# Frogduino_Atmega1284_R2_EasyEDA_Model.net
KiCad netlist of a schematic drawn in EasyEDA Pro
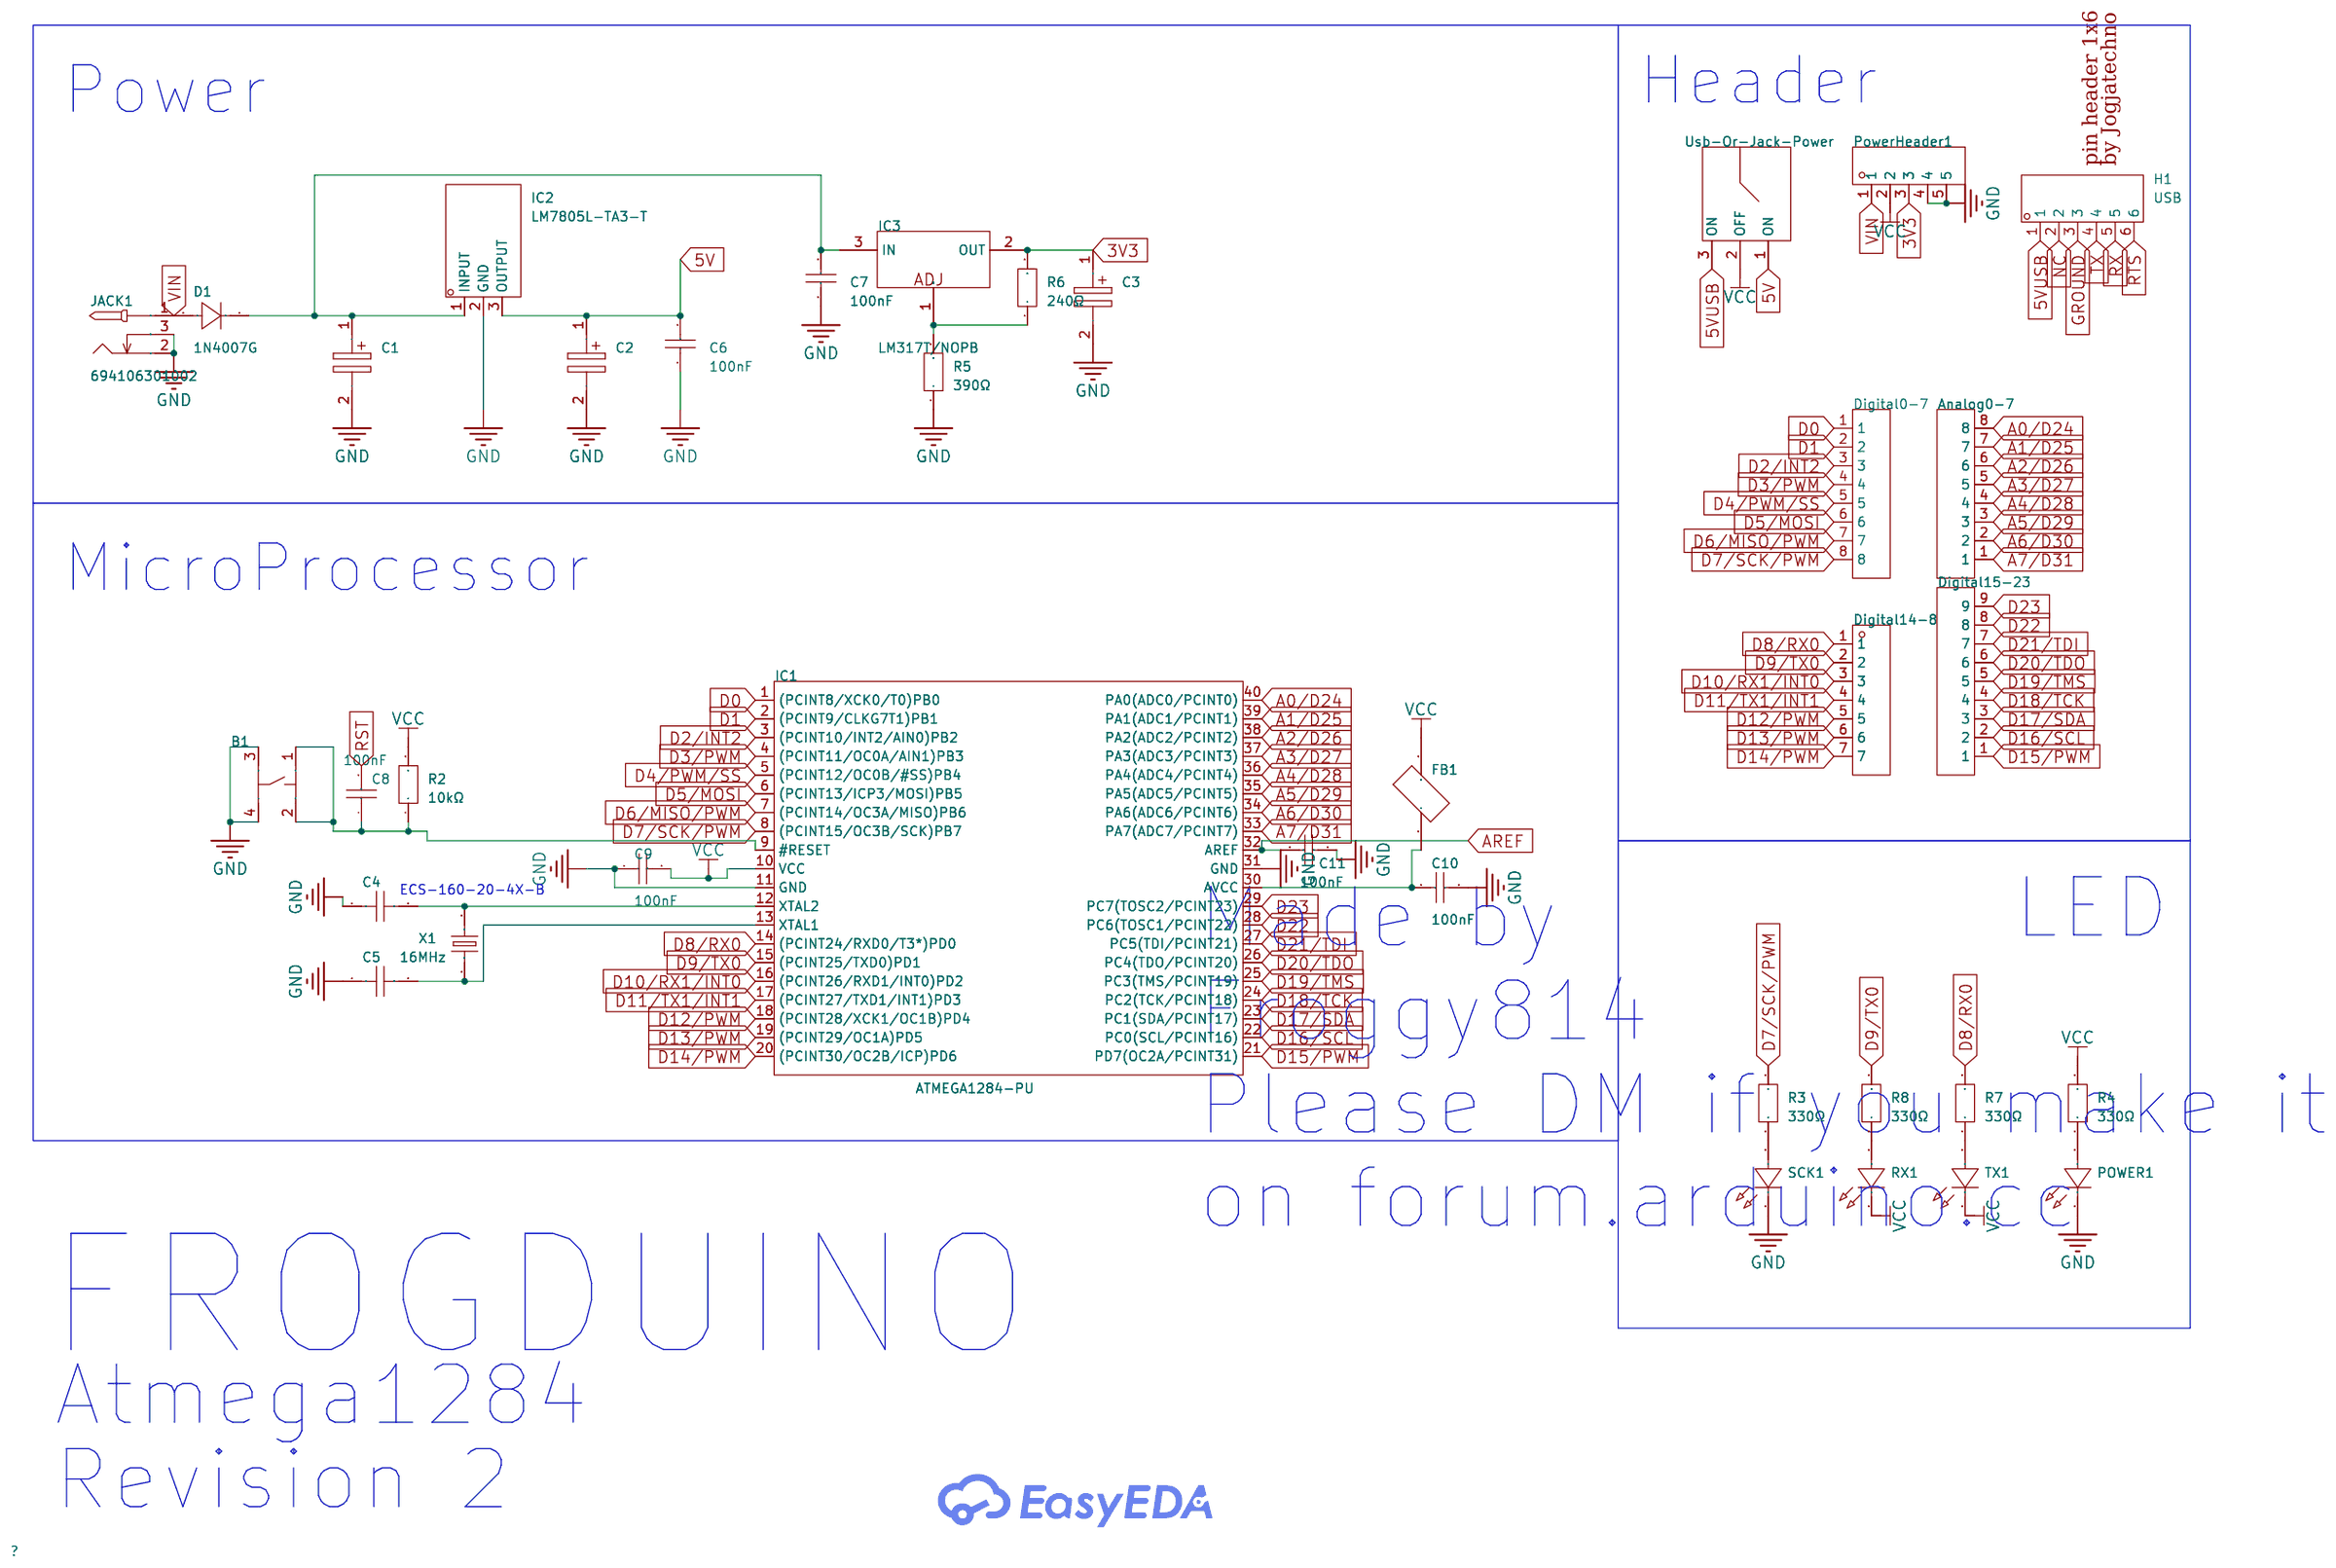
[diagram p0: schematic sheet]

(export (version "E")
  (design (tool "Eeschema 10.0.6"))
  (components
    (comp (ref "Analog0-7")
      (value "排母HDR1X8-2.54")
      (footprint "easyedapro:HDR-TH_8P-P2.54-V-F")
      (libsource (lib "easyedapro") (part "排母HDR1X8-2.54"))
    )
    (comp (ref "B1")
      (value "TS02-66-43-BK-100-SCR-D")
      (footprint "easyedapro:SW-TH_4P-L6.0-W6.0-P4.50-LS6.5")
      (fields (field (name "Manufacturer") "CUI"))
      (libsource (lib "easyedapro") (part "TS02-66-43-BK-100-SCR-D"))
    )
    (comp (ref "C1")
      (value "~")
      (footprint "easyedapro:CAPPM7344X310N")
      (libsource (lib "easyedapro") (part "TAJD107K016SNJV_"))
    )
    (comp (ref "C2")
      (value "~")
      (footprint "easyedapro:CAPPM7344X310N")
      (libsource (lib "easyedapro") (part "TAJD107K016SNJV_"))
    )
    (comp (ref "C3")
      (value "~")
      (footprint "easyedapro:CAPPM7344X310N")
      (libsource (lib "easyedapro") (part "TAJD107K016SNJV_"))
    )
    (comp (ref "C4")
      (value "C0805C220J4HACTU")
      (footprint "easyedapro:C1210")
      (libsource (lib "easyedapro") (part "C1210C220J5GACTU"))
    )
    (comp (ref "C5")
      (value "C0805C220J4HACTU")
      (footprint "easyedapro:C1210")
      (libsource (lib "easyedapro") (part "C1210C220J5GACTU"))
    )
    (comp (ref "C6")
      (value "100nF")
      (footprint "easyedapro:C1206")
      (description "Capacitance:100nF Tolerance:±10% Tolerance:±10% Voltage Rating:100V Temperature Coefficient:X7R")
      (fields (field (name "Manufacturer Part") "1206B104K101CT") (field (name "Manufacturer") "Walsin(华新科)"))
      (libsource (lib "easyedapro") (part "1206B104K101"))
    )
    (comp (ref "C7")
      (value "100nF")
      (footprint "easyedapro:C1206")
      (description "Capacitance:100nF Tolerance:±10% Tolerance:±10% Voltage Rating:100V Temperature Coefficient:X7R")
      (fields (field (name "Manufacturer Part") "1206B104K101CT") (field (name "Manufacturer") "Walsin(华新科)"))
      (libsource (lib "easyedapro") (part "1206B104K101"))
    )
    (comp (ref "C8")
      (value "100nF")
      (footprint "easyedapro:C1206")
      (description "Capacitance:100nF Tolerance:±10% Tolerance:±10% Voltage Rating:100V Temperature Coefficient:X7R")
      (fields (field (name "Manufacturer Part") "1206B104K101CT") (field (name "Manufacturer") "Walsin(华新科)"))
      (libsource (lib "easyedapro") (part "1206B104K101"))
    )
    (comp (ref "C9")
      (value "100nF")
      (footprint "easyedapro:C1206")
      (description "Capacitance:100nF Tolerance:±10% Tolerance:±10% Voltage Rating:100V Temperature Coefficient:X7R")
      (fields (field (name "Manufacturer Part") "1206B104K101CT") (field (name "Manufacturer") "Walsin(华新科)"))
      (libsource (lib "easyedapro") (part "1206B104K101"))
    )
    (comp (ref "C10")
      (value "100nF")
      (footprint "easyedapro:C1206")
      (description "Capacitance:100nF Tolerance:±10% Tolerance:±10% Voltage Rating:100V Temperature Coefficient:X7R")
      (fields (field (name "Manufacturer Part") "1206B104K101CT") (field (name "Manufacturer") "Walsin(华新科)"))
      (libsource (lib "easyedapro") (part "1206B104K101"))
    )
    (comp (ref "C11")
      (value "100nF")
      (footprint "easyedapro:C1206")
      (description "Capacitance:100nF Tolerance:±10% Tolerance:±10% Voltage Rating:100V Temperature Coefficient:X7R")
      (fields (field (name "Manufacturer Part") "1206B104K101CT") (field (name "Manufacturer") "Walsin(华新科)"))
      (libsource (lib "easyedapro") (part "1206B104K101"))
    )
    (comp (ref "D1")
      (value "1N4007G")
      (footprint "easyedapro:DO-41_BD2.4-L4.7-P8.70-D0.6-RD")
      (libsource (lib "easyedapro") (part "1N4007G_C2764732"))
    )
    (comp (ref "Digital0-7")
      (value "排母HDR1X8-2.54")
      (footprint "easyedapro:HDR-TH_8P-P2.54-V-F")
      (libsource (lib "easyedapro") (part "排母HDR1X8-2.54"))
    )
    (comp (ref "Digital14-8")
      (value "2.54-1*7P/30mm(3+24+3)")
      (footprint "easyedapro:HDR-TH_7P-P2.54-V-M-1")
      (libsource (lib "easyedapro") (part "2.54-1*7P/30MM(3+24+3)"))
    )
    (comp (ref "Digital15-23")
      (value "KH-2.54PH180-1X9P-L11.5")
      (footprint "easyedapro:HDR-TH_9P-P2.54-V-M")
      (fields (field (name "Manufacturer") "kinghelm(金航标)"))
      (libsource (lib "easyedapro") (part "KH-2.54PH180-1X9P-L11.5"))
    )
    (comp (ref "FB1")
      (value "~")
      (footprint "easyedapro:FB_28L0138-70R-10")
      (libsource (lib "easyedapro") (part "28L0138-70R-10_"))
    )
    (comp (ref "H1")
      (value "USB")
      (fields
        (field (name "Manufacturer Part") "Headers  Pins1x6P 2.54mm")
        (field (name "Manufacturer") "ReliaPro")
      )
      (libsource (lib "easyedapro") (part "Headers  Pins1x6P 2.54mm"))
    )
    (comp (ref "IC1")
      (value "ATMEGA1284-PU")
      (footprint "easyedapro:CONN-SMD_40P-P2.54_C9900007166")
      (fields (field (name "Manufacturer") "MICROCHIP(美国微芯)"))
      (libsource (lib "easyedapro") (part "ATMEGA1284-PU"))
    )
    (comp (ref "IC2")
      (value "LM7805L-TA3-T")
      (footprint "easyedapro:TO-220IS_L10.16-W4.7-P2.54-L")
      (description "Output Type:-")
      (libsource (lib "easyedapro") (part "LM7805L-TA3-T_C340686"))
    )
    (comp (ref "IC3")
      (value "LM317T/NOPB")
      (footprint "easyedapro:TO-220-3_L10.2-W4.6-P2.54-L")
      (fields (field (name "Manufacturer") "TI(德州仪器)"))
      (libsource (lib "easyedapro") (part "LM317T/NOPB"))
    )
    (comp (ref "JACK1")
      (value "694106301002")
      (footprint "easyedapro:CONN-TH_694106301002")
      (fields (field (name "Manufacturer") "würth Elektronik"))
      (libsource (lib "easyedapro") (part "694106301002"))
    )
    (comp (ref "POWER1")
      (value "SML-811UTT86C")
      (footprint "easyedapro:LED-SMD_L3.4-W1.3-RD")
      (fields (field (name "Manufacturer") "ROHM(罗姆)"))
      (libsource (lib "easyedapro") (part "SML-811UTT86C"))
    )
    (comp (ref "PowerHeader1")
      (value "2.54mm1*5PHeader")
      (footprint "easyedapro:HDR-TH_5P-P2.54-V")
      (fields (field (name "Manufacturer") "ReliaPro"))
      (libsource (lib "easyedapro") (part "2&quot;42 OLED - DIY More"))
    )
    (comp (ref "R2")
      (value "10kΩ")
      (footprint "easyedapro:R2512")
      (fields (field (name "Manufacturer Part") "AS25J1002ET") (field (name "Manufacturer") "Ohmite"))
      (libsource (lib "easyedapro") (part "AS25J1002ET"))
    )
    (comp (ref "R3")
      (value "330Ω")
      (footprint "easyedapro:R2010")
      (fields (field (name "Manufacturer Part") "RC2010JK-07330RL") (field (name "Manufacturer") "YAGEO(国巨)"))
      (libsource (lib "easyedapro") (part "RC2010JK-07330RL"))
    )
    (comp (ref "R4")
      (value "330Ω")
      (footprint "easyedapro:R2010")
      (fields (field (name "Manufacturer Part") "RC2010JK-07330RL") (field (name "Manufacturer") "YAGEO(国巨)"))
      (libsource (lib "easyedapro") (part "RC2010JK-07330RL"))
    )
    (comp (ref "R5")
      (value "390Ω")
      (footprint "easyedapro:R2512")
      (fields
        (field (name "Manufacturer Part") "CRGP2512F390R")
        (field (name "Manufacturer") "TE Connectivity(泰科电子)")
      )
      (libsource (lib "easyedapro") (part "CRGP2512F390R"))
    )
    (comp (ref "R6")
      (value "240Ω")
      (footprint "easyedapro:R2512")
      (fields (field (name "Manufacturer Part") "RK73H3ATTE2400F") (field (name "Manufacturer") "KOA"))
      (libsource (lib "easyedapro") (part "RK73H3ATTE2400F"))
    )
    (comp (ref "R7")
      (value "330Ω")
      (footprint "easyedapro:R2010")
      (fields (field (name "Manufacturer Part") "RC2010JK-07330RL") (field (name "Manufacturer") "YAGEO(国巨)"))
      (libsource (lib "easyedapro") (part "RC2010JK-07330RL"))
    )
    (comp (ref "R8")
      (value "330Ω")
      (footprint "easyedapro:R2010")
      (fields (field (name "Manufacturer Part") "RC2010JK-07330RL") (field (name "Manufacturer") "YAGEO(国巨)"))
      (libsource (lib "easyedapro") (part "RC2010JK-07330RL"))
    )
    (comp (ref "RX1")
      (value "SML-811UTT86C")
      (footprint "easyedapro:LED-SMD_L3.4-W1.3-RD")
      (fields (field (name "Manufacturer") "ROHM(罗姆)"))
      (libsource (lib "easyedapro") (part "SML-811UTT86C"))
    )
    (comp (ref "SCK1")
      (value "SML-811UTT86C")
      (footprint "easyedapro:LED-SMD_L3.4-W1.3-RD")
      (fields (field (name "Manufacturer") "ROHM(罗姆)"))
      (libsource (lib "easyedapro") (part "SML-811UTT86C"))
    )
    (comp (ref "TX1")
      (value "SML-811UTT86C")
      (footprint "easyedapro:LED-SMD_L3.4-W1.3-RD")
      (fields (field (name "Manufacturer") "ROHM(罗姆)"))
      (libsource (lib "easyedapro") (part "SML-811UTT86C"))
    )
    (comp (ref "Usb-Or-Jack-Power")
      (value "pu-mts-103 ON-OFF-ON")
      (footprint "easyedapro:SW-TH_MTS-103")
      (libsource (lib "easyedapro") (part "PU-MTS-103 ON-OFF-ON"))
    )
    (comp (ref "X1")
      (value "16MHz")
      (footprint "easyedapro:HC-49US_L11.5-W4.5-P4.88")
      (fields
        (field (name "Manufacturer Part") "XIHCELNANF-16MHZ")
        (field (name "Manufacturer") "TAITIEN(泰艺电子)")
      )
      (libsource (lib "easyedapro") (part "XIHCELNANF-16MHZ"))
    )
  )
  (nets
    (net (code "1") (name "3V3") (class "Default")
      (node (ref "C3") (pin "1") (pinfunction "+_1") (pintype "bidirectional"))
      (node (ref "IC3") (pin "2") (pinfunction "OUT_2") (pintype "unspecified"))
      (node (ref "PowerHeader1") (pin "3") (pinfunction "3_3") (pintype "input"))
      (node (ref "R6") (pin "2") (pinfunction "2_2") (pintype "input"))
    )
    (net (code "2") (name "5V") (class "Default")
      (node (ref "C2") (pin "1") (pinfunction "+_1") (pintype "bidirectional"))
      (node (ref "C6") (pin "2") (pinfunction "2_2") (pintype "input"))
      (node (ref "IC2") (pin "3") (pinfunction "OUTPUT_3") (pintype "unspecified"))
      (node (ref "Usb-Or-Jack-Power") (pin "1") (pinfunction "ON_1") (pintype "unspecified"))
    )
    (net (code "3") (name "5VUSB") (class "Default")
      (node (ref "H1") (pin "1") (pinfunction "1_1") (pintype "input"))
      (node (ref "Usb-Or-Jack-Power") (pin "3") (pinfunction "ON_3") (pintype "unspecified"))
    )
    (net (code "4") (name "A0{slash}D24") (class "Default")
      (node (ref "Analog0-7") (pin "8") (pinfunction "8_8") (pintype "unspecified"))
      (node (ref "IC1") (pin "40") (pinfunction "PA0(ADC0/PCINT0)_40") (pintype "unspecified"))
    )
    (net (code "5") (name "A1{slash}D25") (class "Default")
      (node (ref "Analog0-7") (pin "7") (pinfunction "7_7") (pintype "unspecified"))
      (node (ref "IC1") (pin "39") (pinfunction "PA1(ADC1/PCINT1)_39") (pintype "unspecified"))
    )
    (net (code "6") (name "A2{slash}D26") (class "Default")
      (node (ref "Analog0-7") (pin "6") (pinfunction "6_6") (pintype "unspecified"))
      (node (ref "IC1") (pin "38") (pinfunction "PA2(ADC2/PCINT2)_38") (pintype "unspecified"))
    )
    (net (code "7") (name "A3{slash}D27") (class "Default")
      (node (ref "Analog0-7") (pin "5") (pinfunction "5_5") (pintype "unspecified"))
      (node (ref "IC1") (pin "37") (pinfunction "PA3(ADC3/PCINT3)_37") (pintype "unspecified"))
    )
    (net (code "8") (name "A4{slash}D28") (class "Default")
      (node (ref "Analog0-7") (pin "4") (pinfunction "4_4") (pintype "unspecified"))
      (node (ref "IC1") (pin "36") (pinfunction "PA4(ADC4/PCINT4)_36") (pintype "unspecified"))
    )
    (net (code "9") (name "A5{slash}D29") (class "Default")
      (node (ref "Analog0-7") (pin "3") (pinfunction "3_3") (pintype "unspecified"))
      (node (ref "IC1") (pin "35") (pinfunction "PA5(ADC5/PCINT5)_35") (pintype "unspecified"))
    )
    (net (code "10") (name "A6{slash}D30") (class "Default")
      (node (ref "Analog0-7") (pin "2") (pinfunction "2_2") (pintype "unspecified"))
      (node (ref "IC1") (pin "34") (pinfunction "PA6(ADC6/PCINT6)_34") (pintype "unspecified"))
    )
    (net (code "11") (name "A7{slash}D31") (class "Default")
      (node (ref "Analog0-7") (pin "1") (pinfunction "1_1") (pintype "unspecified"))
      (node (ref "IC1") (pin "33") (pinfunction "PA7(ADC7/PCINT7)_33") (pintype "unspecified"))
    )
    (net (code "12") (name "AREF") (class "Default")
      (node (ref "C11") (pin "1") (pinfunction "1_1") (pintype "input"))
      (node (ref "IC1") (pin "32") (pinfunction "AREF_32") (pintype "unspecified"))
    )
    (net (code "13") (name "D0") (class "Default")
      (node (ref "Digital0-7") (pin "1") (pinfunction "1_1") (pintype "unspecified"))
      (node (ref "IC1") (pin "1") (pinfunction "(PCINT8/XCK0/T0)PB0_1") (pintype "unspecified"))
    )
    (net (code "14") (name "D1") (class "Default")
      (node (ref "Digital0-7") (pin "2") (pinfunction "2_2") (pintype "unspecified"))
      (node (ref "IC1") (pin "2") (pinfunction "(PCINT9/CLKG7T1)PB1_2") (pintype "unspecified"))
    )
    (net (code "15") (name "D2{slash}INT2") (class "Default")
      (node (ref "Digital0-7") (pin "3") (pinfunction "3_3") (pintype "unspecified"))
      (node (ref "IC1") (pin "3") (pinfunction "(PCINT10/INT2/AIN0)PB2_3") (pintype "unspecified"))
    )
    (net (code "16") (name "D3{slash}PWM") (class "Default")
      (node (ref "Digital0-7") (pin "4") (pinfunction "4_4") (pintype "unspecified"))
      (node (ref "IC1") (pin "4") (pinfunction "(PCINT11/OC0A/AIN1)PB3_4") (pintype "unspecified"))
    )
    (net (code "17") (name "D4{slash}PWM{slash}SS") (class "Default")
      (node (ref "Digital0-7") (pin "5") (pinfunction "5_5") (pintype "unspecified"))
      (node (ref "IC1") (pin "5") (pinfunction "(PCINT12/OC0B/#SS)PB4_5") (pintype "unspecified"))
    )
    (net (code "18") (name "D5{slash}MOSI") (class "Default")
      (node (ref "Digital0-7") (pin "6") (pinfunction "6_6") (pintype "unspecified"))
      (node (ref "IC1") (pin "6") (pinfunction "(PCINT13/ICP3/MOSI)PB5_6") (pintype "unspecified"))
    )
    (net (code "19") (name "D6{slash}MISO{slash}PWM") (class "Default")
      (node (ref "Digital0-7") (pin "7") (pinfunction "7_7") (pintype "unspecified"))
      (node (ref "IC1") (pin "7") (pinfunction "(PCINT14/OC3A/MISO)PB6_7") (pintype "unspecified"))
    )
    (net (code "20") (name "D7{slash}SCK{slash}PWM") (class "Default")
      (node (ref "Digital0-7") (pin "8") (pinfunction "8_8") (pintype "unspecified"))
      (node (ref "IC1") (pin "8") (pinfunction "(PCINT15/OC3B/SCK)PB7_8") (pintype "unspecified"))
      (node (ref "R3") (pin "2") (pinfunction "2_2") (pintype "unspecified"))
    )
    (net (code "21") (name "D8{slash}RX0") (class "Default")
      (node (ref "Digital14-8") (pin "1") (pinfunction "1_1") (pintype "unspecified"))
      (node (ref "IC1") (pin "14") (pinfunction "(PCINT24/RXD0/T3*)PD0_14") (pintype "unspecified"))
      (node (ref "R7") (pin "2") (pinfunction "2_2") (pintype "unspecified"))
    )
    (net (code "22") (name "D9{slash}TX0") (class "Default")
      (node (ref "Digital14-8") (pin "2") (pinfunction "2_2") (pintype "unspecified"))
      (node (ref "IC1") (pin "15") (pinfunction "(PCINT25/TXD0)PD1_15") (pintype "unspecified"))
      (node (ref "R8") (pin "2") (pinfunction "2_2") (pintype "unspecified"))
    )
    (net (code "23") (name "D10{slash}RX1{slash}INT0") (class "Default")
      (node (ref "Digital14-8") (pin "3") (pinfunction "3_3") (pintype "unspecified"))
      (node (ref "IC1") (pin "16") (pinfunction "(PCINT26/RXD1/INT0)PD2_16") (pintype "unspecified"))
    )
    (net (code "24") (name "D11{slash}TX1{slash}INT1") (class "Default")
      (node (ref "Digital14-8") (pin "4") (pinfunction "4_4") (pintype "unspecified"))
      (node (ref "IC1") (pin "17") (pinfunction "(PCINT27/TXD1/INT1)PD3_17") (pintype "unspecified"))
    )
    (net (code "25") (name "D12{slash}PWM") (class "Default")
      (node (ref "Digital14-8") (pin "5") (pinfunction "5_5") (pintype "unspecified"))
      (node (ref "IC1") (pin "18") (pinfunction "(PCINT28/XCK1/OC1B)PD4_18") (pintype "unspecified"))
    )
    (net (code "26") (name "D13{slash}PWM") (class "Default")
      (node (ref "Digital14-8") (pin "6") (pinfunction "6_6") (pintype "unspecified"))
      (node (ref "IC1") (pin "19") (pinfunction "(PCINT29/OC1A)PD5_19") (pintype "unspecified"))
    )
    (net (code "27") (name "D14{slash}PWM") (class "Default")
      (node (ref "Digital14-8") (pin "7") (pinfunction "7_7") (pintype "unspecified"))
      (node (ref "IC1") (pin "20") (pinfunction "(PCINT30/OC2B/ICP)PD6_20") (pintype "unspecified"))
    )
    (net (code "28") (name "D15{slash}PWM") (class "Default")
      (node (ref "Digital15-23") (pin "1") (pinfunction "1_1") (pintype "unspecified"))
      (node (ref "IC1") (pin "21") (pinfunction "PD7(OC2A/PCINT31)_21") (pintype "unspecified"))
    )
    (net (code "29") (name "D16{slash}SCL") (class "Default")
      (node (ref "Digital15-23") (pin "2") (pinfunction "2_2") (pintype "unspecified"))
      (node (ref "IC1") (pin "22") (pinfunction "PC0(SCL/PCINT16)_22") (pintype "unspecified"))
    )
    (net (code "30") (name "D17{slash}SDA") (class "Default")
      (node (ref "Digital15-23") (pin "3") (pinfunction "3_3") (pintype "unspecified"))
      (node (ref "IC1") (pin "23") (pinfunction "PC1(SDA/PCINT17)_23") (pintype "unspecified"))
    )
    (net (code "31") (name "D18{slash}TCK") (class "Default")
      (node (ref "Digital15-23") (pin "4") (pinfunction "4_4") (pintype "unspecified"))
      (node (ref "IC1") (pin "24") (pinfunction "PC2(TCK/PCINT18)_24") (pintype "unspecified"))
    )
    (net (code "32") (name "D19{slash}TMS") (class "Default")
      (node (ref "Digital15-23") (pin "5") (pinfunction "5_5") (pintype "unspecified"))
      (node (ref "IC1") (pin "25") (pinfunction "PC3(TMS/PCINT19)_25") (pintype "unspecified"))
    )
    (net (code "33") (name "D20{slash}TDO") (class "Default")
      (node (ref "Digital15-23") (pin "6") (pinfunction "6_6") (pintype "unspecified"))
      (node (ref "IC1") (pin "26") (pinfunction "PC4(TDO/PCINT20)_26") (pintype "unspecified"))
    )
    (net (code "34") (name "D21{slash}TDI") (class "Default")
      (node (ref "Digital15-23") (pin "7") (pinfunction "7_7") (pintype "unspecified"))
      (node (ref "IC1") (pin "27") (pinfunction "PC5(TDI/PCINT21)_27") (pintype "unspecified"))
    )
    (net (code "35") (name "D22") (class "Default")
      (node (ref "Digital15-23") (pin "8") (pinfunction "8_8") (pintype "unspecified"))
      (node (ref "IC1") (pin "28") (pinfunction "PC6(TOSC1/PCINT22)_28") (pintype "unspecified"))
    )
    (net (code "36") (name "D23") (class "Default")
      (node (ref "Digital15-23") (pin "9") (pinfunction "9_9") (pintype "unspecified"))
      (node (ref "IC1") (pin "29") (pinfunction "PC7(TOSC2/PCINT23)_29") (pintype "unspecified"))
    )
    (net (code "37") (name "GND") (class "Default")
      (node (ref "B1") (pin "3") (pinfunction "3_3") (pintype "unspecified"))
      (node (ref "B1") (pin "4") (pinfunction "4_4") (pintype "unspecified"))
      (node (ref "C1") (pin "2") (pinfunction "-_2") (pintype "bidirectional"))
      (node (ref "C10") (pin "2") (pinfunction "2_2") (pintype "input"))
      (node (ref "C11") (pin "2") (pinfunction "2_2") (pintype "input"))
      (node (ref "C2") (pin "2") (pinfunction "-_2") (pintype "bidirectional"))
      (node (ref "C3") (pin "2") (pinfunction "-_2") (pintype "bidirectional"))
      (node (ref "C4") (pin "1") (pinfunction "1_1") (pintype "unspecified"))
      (node (ref "C5") (pin "1") (pinfunction "1_1") (pintype "unspecified"))
      (node (ref "C6") (pin "1") (pinfunction "1_1") (pintype "input"))
      (node (ref "C7") (pin "1") (pinfunction "1_1") (pintype "input"))
      (node (ref "C9") (pin "1") (pinfunction "1_1") (pintype "input"))
      (node (ref "IC1") (pin "11") (pinfunction "GND_11") (pintype "unspecified"))
      (node (ref "IC1") (pin "31") (pinfunction "GND_31") (pintype "unspecified"))
      (node (ref "IC2") (pin "2") (pinfunction "GND_2") (pintype "unspecified"))
      (node (ref "JACK1") (pin "2") (pinfunction "2_2") (pintype "input"))
      (node (ref "JACK1") (pin "3") (pinfunction "3_3") (pintype "input"))
      (node (ref "POWER1") (pin "1") (pinfunction "K_1") (pintype "unspecified"))
      (node (ref "PowerHeader1") (pin "4") (pinfunction "4_4") (pintype "input"))
      (node (ref "PowerHeader1") (pin "5") (pinfunction "5_5") (pintype "input"))
      (node (ref "R5") (pin "1") (pinfunction "1_1") (pintype "unspecified"))
      (node (ref "SCK1") (pin "1") (pinfunction "K_1") (pintype "unspecified"))
    )
    (net (code "38") (name "GROUND") (class "Default")
      (node (ref "H1") (pin "3") (pinfunction "3_3") (pintype "input"))
    )
    (net (code "39") (name "NC") (class "Default")
      (node (ref "H1") (pin "2") (pinfunction "2_2") (pintype "input"))
    )
    (net (code "40") (name "Net-(C1-+)") (class "Default")
      (node (ref "C1") (pin "1") (pinfunction "+_1") (pintype "bidirectional"))
      (node (ref "C7") (pin "2") (pinfunction "2_2") (pintype "input"))
      (node (ref "D1") (pin "1") (pinfunction "K_1") (pintype "input"))
      (node (ref "IC2") (pin "1") (pinfunction "INPUT_1") (pintype "unspecified"))
      (node (ref "IC3") (pin "3") (pinfunction "IN_3") (pintype "unspecified"))
    )
    (net (code "41") (name "Net-(IC1-#RESET)") (class "Default")
      (node (ref "B1") (pin "1") (pinfunction "1_1") (pintype "unspecified"))
      (node (ref "B1") (pin "2") (pinfunction "2_2") (pintype "unspecified"))
      (node (ref "C8") (pin "1") (pinfunction "1_1") (pintype "input"))
      (node (ref "IC1") (pin "9") (pinfunction "#RESET_9") (pintype "unspecified"))
      (node (ref "R2") (pin "1") (pinfunction "1_1") (pintype "unspecified"))
    )
    (net (code "42") (name "Net-(IC1-AVCC)") (class "Default")
      (node (ref "C10") (pin "1") (pinfunction "1_1") (pintype "input"))
      (node (ref "FB1") (pin "1") (pinfunction "1_1") (pintype "input"))
      (node (ref "IC1") (pin "30") (pinfunction "AVCC_30") (pintype "unspecified"))
    )
    (net (code "43") (name "Net-(IC1-XTAL1)") (class "Default")
      (node (ref "C5") (pin "2") (pinfunction "2_2") (pintype "unspecified"))
      (node (ref "IC1") (pin "13") (pinfunction "XTAL1_13") (pintype "unspecified"))
      (node (ref "X1") (pin "1") (pinfunction "1_1") (pintype "unspecified"))
    )
    (net (code "44") (name "Net-(IC1-XTAL2)") (class "Default")
      (node (ref "C4") (pin "2") (pinfunction "2_2") (pintype "unspecified"))
      (node (ref "IC1") (pin "12") (pinfunction "XTAL2_12") (pintype "unspecified"))
      (node (ref "X1") (pin "2") (pinfunction "2_2") (pintype "unspecified"))
    )
    (net (code "45") (name "Net-(IC3-ADJ)") (class "Default")
      (node (ref "IC3") (pin "1") (pinfunction "ADJ_1") (pintype "unspecified"))
      (node (ref "R5") (pin "2") (pinfunction "2_2") (pintype "unspecified"))
      (node (ref "R6") (pin "1") (pinfunction "1_1") (pintype "input"))
    )
    (net (code "46") (name "Net-(POWER1-A)") (class "Default")
      (node (ref "POWER1") (pin "2") (pinfunction "A_2") (pintype "unspecified"))
      (node (ref "R4") (pin "1") (pinfunction "1_1") (pintype "unspecified"))
    )
    (net (code "47") (name "Net-(RX1-A)") (class "Default")
      (node (ref "R8") (pin "1") (pinfunction "1_1") (pintype "unspecified"))
      (node (ref "RX1") (pin "2") (pinfunction "A_2") (pintype "unspecified"))
    )
    (net (code "48") (name "Net-(SCK1-A)") (class "Default")
      (node (ref "R3") (pin "1") (pinfunction "1_1") (pintype "unspecified"))
      (node (ref "SCK1") (pin "2") (pinfunction "A_2") (pintype "unspecified"))
    )
    (net (code "49") (name "Net-(TX1-A)") (class "Default")
      (node (ref "R7") (pin "1") (pinfunction "1_1") (pintype "unspecified"))
      (node (ref "TX1") (pin "2") (pinfunction "A_2") (pintype "unspecified"))
    )
    (net (code "50") (name "RST") (class "Default")
      (node (ref "C8") (pin "2") (pinfunction "2_2") (pintype "input"))
    )
    (net (code "51") (name "RTS") (class "Default")
      (node (ref "H1") (pin "6") (pinfunction "6_6") (pintype "input"))
    )
    (net (code "52") (name "RX") (class "Default")
      (node (ref "H1") (pin "5") (pinfunction "5_5") (pintype "input"))
    )
    (net (code "53") (name "TX") (class "Default")
      (node (ref "H1") (pin "4") (pinfunction "4_4") (pintype "input"))
    )
    (net (code "54") (name "VCC") (class "Default")
      (node (ref "C9") (pin "2") (pinfunction "2_2") (pintype "input"))
      (node (ref "FB1") (pin "2") (pinfunction "2_2") (pintype "input"))
      (node (ref "IC1") (pin "10") (pinfunction "VCC_10") (pintype "unspecified"))
      (node (ref "PowerHeader1") (pin "2") (pinfunction "2_2") (pintype "input"))
      (node (ref "R2") (pin "2") (pinfunction "2_2") (pintype "unspecified"))
      (node (ref "R4") (pin "2") (pinfunction "2_2") (pintype "unspecified"))
      (node (ref "RX1") (pin "1") (pinfunction "K_1") (pintype "unspecified"))
      (node (ref "TX1") (pin "1") (pinfunction "K_1") (pintype "unspecified"))
      (node (ref "Usb-Or-Jack-Power") (pin "2") (pinfunction "OFF_2") (pintype "unspecified"))
    )
    (net (code "55") (name "VIN") (class "Default")
      (node (ref "D1") (pin "2") (pinfunction "A_2") (pintype "input"))
      (node (ref "JACK1") (pin "1") (pinfunction "1_1") (pintype "input"))
      (node (ref "PowerHeader1") (pin "1") (pinfunction "1_1") (pintype "input"))
    )
  )
)
